# main_board.net
KiCad netlist of a schematic drawn in EAGLE
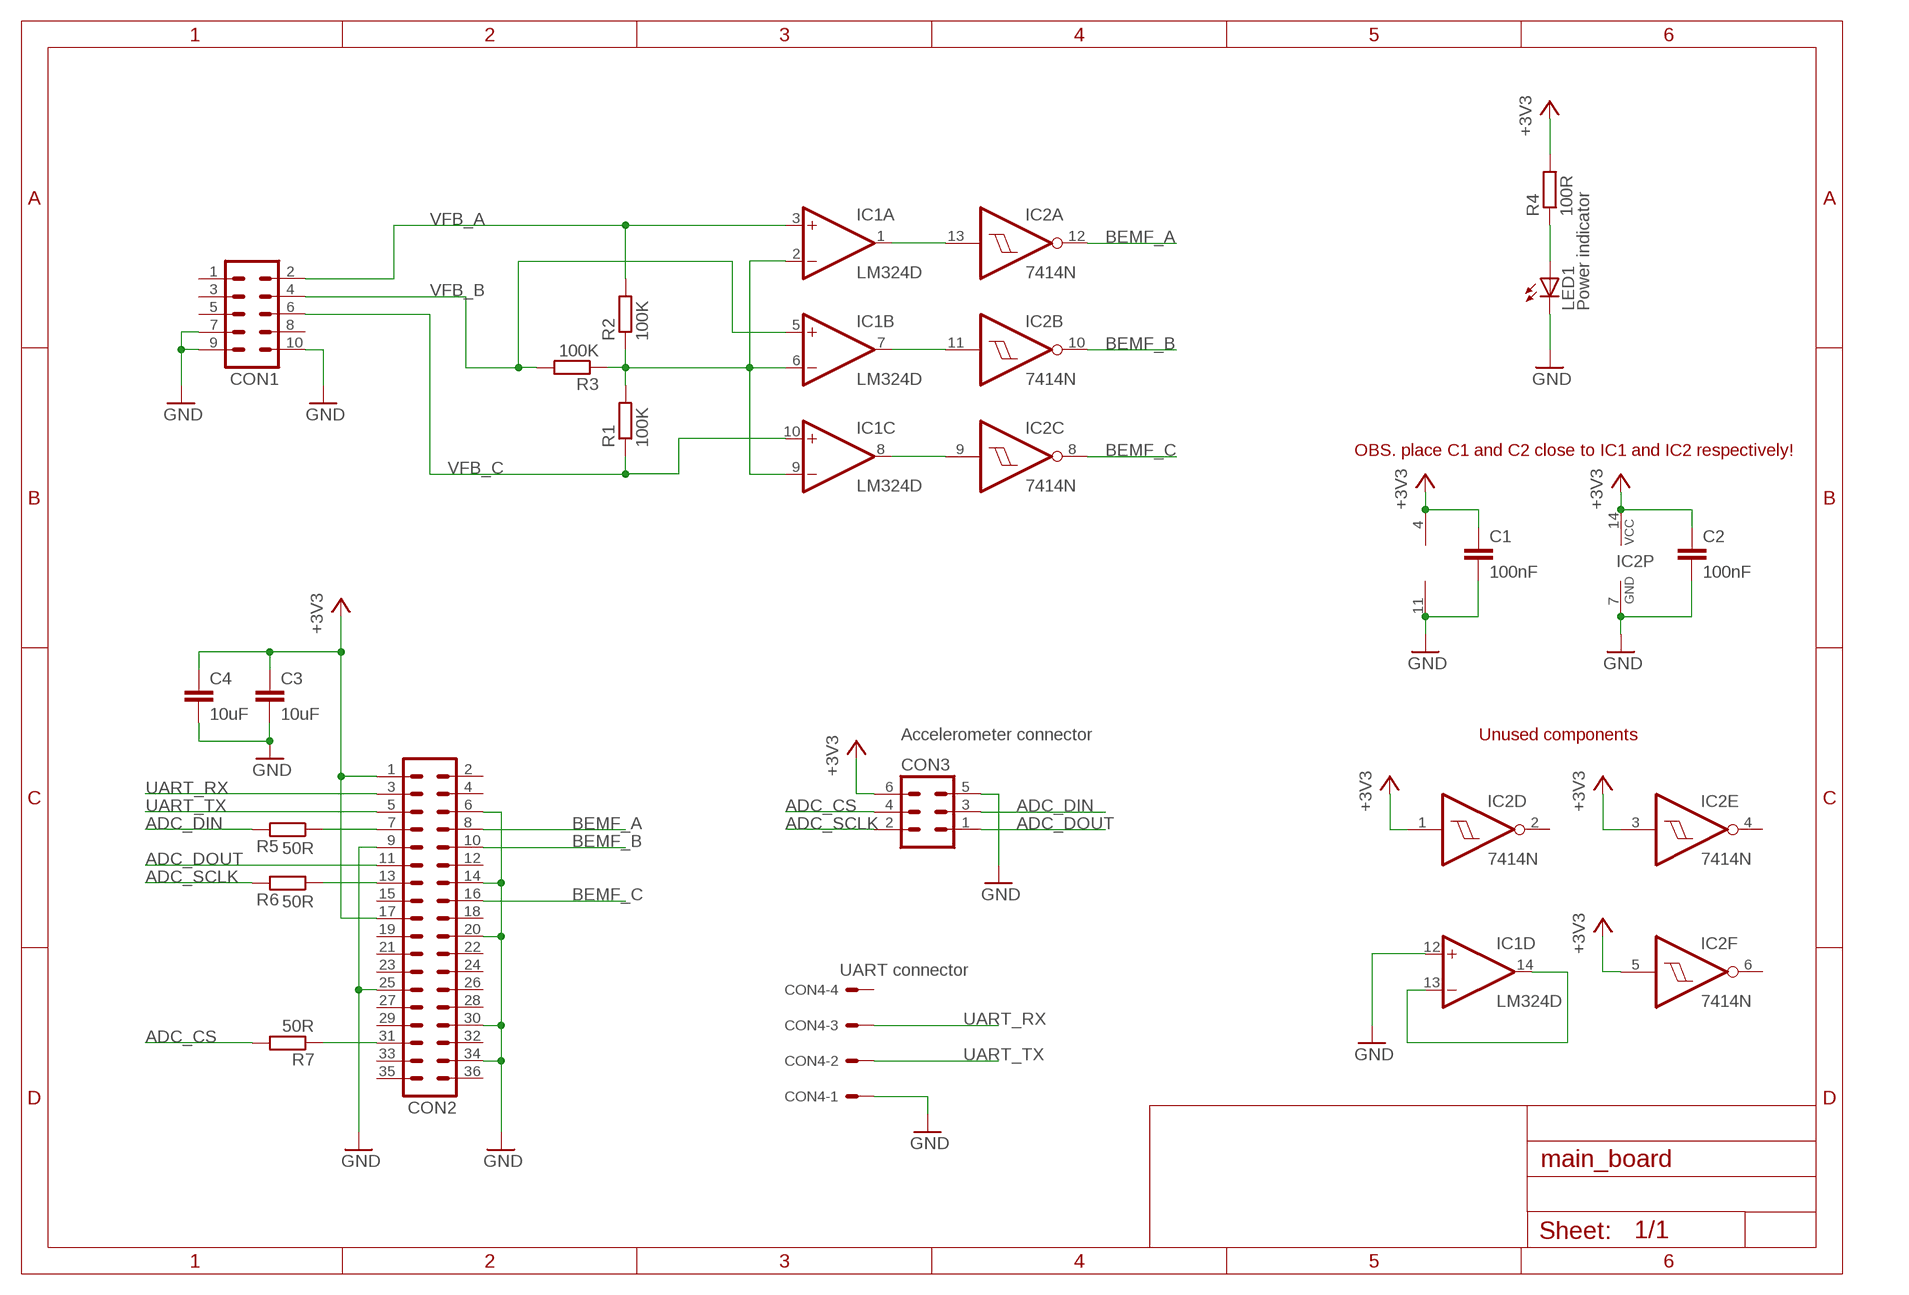
[diagram p0: schematic, sheet 1]

(export (version "E")
  (design (tool "Eeschema 10.0.6"))
  (components
    (comp (ref "C1")
      (value "100nF")
      (footprint "eagle-import:C0805K")
      (libsource (lib "eagle-import") (part "C-EUC0805K"))
    )
    (comp (ref "C2")
      (value "100nF")
      (footprint "eagle-import:C0805K")
      (libsource (lib "eagle-import") (part "C-EUC0805K"))
    )
    (comp (ref "C3")
      (value "10uF")
      (footprint "eagle-import:C1206K")
      (libsource (lib "eagle-import") (part "C-EUC1206K"))
    )
    (comp (ref "C4")
      (value "10uF")
      (footprint "eagle-import:C1206K")
      (libsource (lib "eagle-import") (part "C-EUC1206K"))
    )
    (comp (ref "CON1")
      (value "MA05-2")
      (footprint "eagle-import:MA05-2")
      (libsource (lib "eagle-import") (part "MA05-2"))
    )
    (comp (ref "CON2")
      (value "MA18-2")
      (footprint "eagle-import:MA18-2")
      (libsource (lib "eagle-import") (part "MA18-2"))
    )
    (comp (ref "CON3")
      (value "Accelerometer connector")
      (footprint "eagle-import:ML6")
      (libsource (lib "eagle-import") (part "ML6"))
    )
    (comp (ref "CON4")
      (value "UART connector")
      (footprint "eagle-import:6410-04")
      (libsource (lib "eagle-import") (part "22-?-0427-2041"))
    )
    (comp (ref "IC1")
      (value "LM324D")
      (footprint "eagle-import:SO14")
      (libsource (lib "eagle-import") (part "LM324D"))
    )
    (comp (ref "IC2")
      (value "7414N")
      (footprint "eagle-import:DIL14")
      (libsource (lib "eagle-import") (part "7414N"))
    )
    (comp (ref "LED1")
      (value "Power indicator")
      (footprint "eagle-import:CHIP-LED0805")
      (libsource (lib "eagle-import") (part "LEDCHIP-LED0805"))
    )
    (comp (ref "R1")
      (value "100K")
      (footprint "eagle-import:R0805")
      (libsource (lib "eagle-import") (part "R-EU_R0805"))
    )
    (comp (ref "R2")
      (value "100K")
      (footprint "eagle-import:R0805")
      (libsource (lib "eagle-import") (part "R-EU_R0805"))
    )
    (comp (ref "R3")
      (value "100K")
      (footprint "eagle-import:R0805")
      (libsource (lib "eagle-import") (part "R-EU_R0805"))
    )
    (comp (ref "R4")
      (value "100R")
      (footprint "eagle-import:R0805")
      (libsource (lib "eagle-import") (part "R-EU_R0805"))
    )
    (comp (ref "R5")
      (value "50R")
      (footprint "eagle-import:R0805")
      (libsource (lib "eagle-import") (part "R-EU_R0805"))
    )
    (comp (ref "R6")
      (value "50R")
      (footprint "eagle-import:R0805")
      (libsource (lib "eagle-import") (part "R-EU_R0805"))
    )
    (comp (ref "R7")
      (value "50R")
      (footprint "eagle-import:R0805")
      (libsource (lib "eagle-import") (part "R-EU_R0805"))
    )
  )
  (nets
    (net (code "1") (name "+3V3") (class "Default")
      (node (ref "C1") (pin "1") (pinfunction "1_1") (pintype "passive"))
      (node (ref "C2") (pin "1") (pinfunction "1_1") (pintype "passive"))
      (node (ref "C3") (pin "1") (pinfunction "1_1") (pintype "passive"))
      (node (ref "C4") (pin "1") (pinfunction "1_1") (pintype "passive"))
      (node (ref "CON2") (pin "1") (pinfunction "1_1") (pintype "passive"))
      (node (ref "CON2") (pin "17") (pinfunction "17_17") (pintype "passive"))
      (node (ref "CON3") (pin "6") (pinfunction "6_6") (pintype "passive"))
      (node (ref "IC1") (pin "4") (pinfunction "V+_4") (pintype "power_in"))
      (node (ref "IC2") (pin "1") (pinfunction "I_1") (pintype "input"))
      (node (ref "IC2") (pin "14") (pinfunction "VCC_14") (pintype "power_in"))
      (node (ref "IC2") (pin "3") (pinfunction "I_3") (pintype "input"))
      (node (ref "IC2") (pin "5") (pinfunction "I_5") (pintype "input"))
      (node (ref "R4") (pin "2") (pinfunction "2_2") (pintype "passive"))
    )
    (net (code "2") (name "/ADC_CS") (class "Default")
      (node (ref "CON3") (pin "4") (pinfunction "4_4") (pintype "passive"))
      (node (ref "R7") (pin "2") (pinfunction "2_2") (pintype "passive"))
    )
    (net (code "3") (name "/ADC_DIN") (class "Default")
      (node (ref "CON3") (pin "3") (pinfunction "3_3") (pintype "passive"))
      (node (ref "R5") (pin "2") (pinfunction "2_2") (pintype "passive"))
    )
    (net (code "4") (name "/ADC_DOUT") (class "Default")
      (node (ref "CON2") (pin "11") (pinfunction "11_11") (pintype "passive"))
      (node (ref "CON3") (pin "1") (pinfunction "1_1") (pintype "passive"))
    )
    (net (code "5") (name "/ADC_SCLK") (class "Default")
      (node (ref "CON3") (pin "2") (pinfunction "2_2") (pintype "passive"))
      (node (ref "R6") (pin "2") (pinfunction "2_2") (pintype "passive"))
    )
    (net (code "6") (name "/BEMF_A") (class "Default")
      (node (ref "CON2") (pin "8") (pinfunction "8_8") (pintype "passive"))
      (node (ref "IC2") (pin "12") (pinfunction "O_12") (pintype "output"))
    )
    (net (code "7") (name "/BEMF_B") (class "Default")
      (node (ref "CON2") (pin "10") (pinfunction "10_10") (pintype "passive"))
      (node (ref "IC2") (pin "10") (pinfunction "O_10") (pintype "output"))
    )
    (net (code "8") (name "/BEMF_C") (class "Default")
      (node (ref "CON2") (pin "16") (pinfunction "16_16") (pintype "passive"))
      (node (ref "IC2") (pin "8") (pinfunction "O_8") (pintype "output"))
    )
    (net (code "9") (name "/UART_RX") (class "Default")
      (node (ref "CON2") (pin "3") (pinfunction "3_3") (pintype "passive"))
      (node (ref "CON4") (pin "3") (pinfunction "S_3") (pintype "passive"))
    )
    (net (code "10") (name "/UART_TX") (class "Default")
      (node (ref "CON2") (pin "5") (pinfunction "5_5") (pintype "passive"))
      (node (ref "CON4") (pin "2") (pinfunction "S_2") (pintype "passive"))
    )
    (net (code "11") (name "/VFB_A") (class "Default")
      (node (ref "CON1") (pin "2") (pinfunction "2_2") (pintype "passive"))
      (node (ref "IC1") (pin "3") (pinfunction "+IN_3") (pintype "input"))
      (node (ref "R2") (pin "2") (pinfunction "2_2") (pintype "passive"))
    )
    (net (code "12") (name "/VFB_B") (class "Default")
      (node (ref "CON1") (pin "4") (pinfunction "4_4") (pintype "passive"))
      (node (ref "IC1") (pin "5") (pinfunction "+IN_5") (pintype "input"))
      (node (ref "R3") (pin "2") (pinfunction "2_2") (pintype "passive"))
    )
    (net (code "13") (name "/VFB_C") (class "Default")
      (node (ref "CON1") (pin "6") (pinfunction "6_6") (pintype "passive"))
      (node (ref "IC1") (pin "10") (pinfunction "+IN_10") (pintype "input"))
      (node (ref "R1") (pin "1") (pinfunction "1_1") (pintype "passive"))
    )
    (net (code "14") (name "GND") (class "Default")
      (node (ref "C1") (pin "2") (pinfunction "2_2") (pintype "passive"))
      (node (ref "C2") (pin "2") (pinfunction "2_2") (pintype "passive"))
      (node (ref "C3") (pin "2") (pinfunction "2_2") (pintype "passive"))
      (node (ref "C4") (pin "2") (pinfunction "2_2") (pintype "passive"))
      (node (ref "CON1") (pin "10") (pinfunction "10_10") (pintype "passive"))
      (node (ref "CON1") (pin "7") (pinfunction "7_7") (pintype "passive"))
      (node (ref "CON1") (pin "9") (pinfunction "9_9") (pintype "passive"))
      (node (ref "CON2") (pin "14") (pinfunction "14_14") (pintype "passive"))
      (node (ref "CON2") (pin "20") (pinfunction "20_20") (pintype "passive"))
      (node (ref "CON2") (pin "25") (pinfunction "25_25") (pintype "passive"))
      (node (ref "CON2") (pin "30") (pinfunction "30_30") (pintype "passive"))
      (node (ref "CON2") (pin "34") (pinfunction "34_34") (pintype "passive"))
      (node (ref "CON2") (pin "6") (pinfunction "6_6") (pintype "passive"))
      (node (ref "CON2") (pin "9") (pinfunction "9_9") (pintype "passive"))
      (node (ref "CON3") (pin "5") (pinfunction "5_5") (pintype "passive"))
      (node (ref "CON4") (pin "1") (pinfunction "S_1") (pintype "passive"))
      (node (ref "IC1") (pin "11") (pinfunction "V-_11") (pintype "power_in"))
      (node (ref "IC1") (pin "12") (pinfunction "+IN_12") (pintype "input"))
      (node (ref "IC2") (pin "7") (pinfunction "GND_7") (pintype "power_in"))
      (node (ref "LED1") (pin "C") (pinfunction "C_C") (pintype "passive"))
    )
    (net (code "15") (name "Net-(CON2-Pad7)") (class "Default")
      (node (ref "CON2") (pin "7") (pinfunction "7_7") (pintype "passive"))
      (node (ref "R5") (pin "1") (pinfunction "1_1") (pintype "passive"))
    )
    (net (code "16") (name "Net-(CON2-Pad13)") (class "Default")
      (node (ref "CON2") (pin "13") (pinfunction "13_13") (pintype "passive"))
      (node (ref "R6") (pin "1") (pinfunction "1_1") (pintype "passive"))
    )
    (net (code "17") (name "Net-(CON2-Pad31)") (class "Default")
      (node (ref "CON2") (pin "31") (pinfunction "31_31") (pintype "passive"))
      (node (ref "R7") (pin "1") (pinfunction "1_1") (pintype "passive"))
    )
    (net (code "18") (name "Net-(IC1A--IN)") (class "Default")
      (node (ref "IC1") (pin "2") (pinfunction "-IN_2") (pintype "input"))
      (node (ref "IC1") (pin "6") (pinfunction "-IN_6") (pintype "input"))
      (node (ref "IC1") (pin "9") (pinfunction "-IN_9") (pintype "input"))
      (node (ref "R1") (pin "2") (pinfunction "2_2") (pintype "passive"))
      (node (ref "R2") (pin "1") (pinfunction "1_1") (pintype "passive"))
      (node (ref "R3") (pin "1") (pinfunction "1_1") (pintype "passive"))
    )
    (net (code "19") (name "Net-(IC1A-OUT)") (class "Default")
      (node (ref "IC1") (pin "1") (pinfunction "OUT_1") (pintype "output"))
      (node (ref "IC2") (pin "13") (pinfunction "I_13") (pintype "input"))
    )
    (net (code "20") (name "Net-(IC1B-OUT)") (class "Default")
      (node (ref "IC1") (pin "7") (pinfunction "OUT_7") (pintype "output"))
      (node (ref "IC2") (pin "11") (pinfunction "I_11") (pintype "input"))
    )
    (net (code "21") (name "Net-(IC1C-OUT)") (class "Default")
      (node (ref "IC1") (pin "8") (pinfunction "OUT_8") (pintype "output"))
      (node (ref "IC2") (pin "9") (pinfunction "I_9") (pintype "input"))
    )
    (net (code "22") (name "Net-(IC1D--IN)") (class "Default")
      (node (ref "IC1") (pin "13") (pinfunction "-IN_13") (pintype "input"))
      (node (ref "IC1") (pin "14") (pinfunction "OUT_14") (pintype "output"))
    )
    (net (code "23") (name "Net-(LED1-PadA)") (class "Default")
      (node (ref "LED1") (pin "A") (pinfunction "A_A") (pintype "passive"))
      (node (ref "R4") (pin "1") (pinfunction "1_1") (pintype "passive"))
    )
    (net (code "24") (name "unconnected-(CON1-Pad1)") (class "Default")
      (node (ref "CON1") (pin "1") (pinfunction "1_1") (pintype "passive"))
    )
    (net (code "25") (name "unconnected-(CON1-Pad3)") (class "Default")
      (node (ref "CON1") (pin "3") (pinfunction "3_3") (pintype "passive"))
    )
    (net (code "26") (name "unconnected-(CON1-Pad5)") (class "Default")
      (node (ref "CON1") (pin "5") (pinfunction "5_5") (pintype "passive"))
    )
    (net (code "27") (name "unconnected-(CON1-Pad8)") (class "Default")
      (node (ref "CON1") (pin "8") (pinfunction "8_8") (pintype "passive"))
    )
    (net (code "28") (name "unconnected-(CON2-Pad2)") (class "Default")
      (node (ref "CON2") (pin "2") (pinfunction "2_2") (pintype "passive"))
    )
    (net (code "29") (name "unconnected-(CON2-Pad4)") (class "Default")
      (node (ref "CON2") (pin "4") (pinfunction "4_4") (pintype "passive"))
    )
    (net (code "30") (name "unconnected-(CON2-Pad12)") (class "Default")
      (node (ref "CON2") (pin "12") (pinfunction "12_12") (pintype "passive"))
    )
    (net (code "31") (name "unconnected-(CON2-Pad15)") (class "Default")
      (node (ref "CON2") (pin "15") (pinfunction "15_15") (pintype "passive"))
    )
    (net (code "32") (name "unconnected-(CON2-Pad18)") (class "Default")
      (node (ref "CON2") (pin "18") (pinfunction "18_18") (pintype "passive"))
    )
    (net (code "33") (name "unconnected-(CON2-Pad19)") (class "Default")
      (node (ref "CON2") (pin "19") (pinfunction "19_19") (pintype "passive"))
    )
    (net (code "34") (name "unconnected-(CON2-Pad21)") (class "Default")
      (node (ref "CON2") (pin "21") (pinfunction "21_21") (pintype "passive"))
    )
    (net (code "35") (name "unconnected-(CON2-Pad22)") (class "Default")
      (node (ref "CON2") (pin "22") (pinfunction "22_22") (pintype "passive"))
    )
    (net (code "36") (name "unconnected-(CON2-Pad23)") (class "Default")
      (node (ref "CON2") (pin "23") (pinfunction "23_23") (pintype "passive"))
    )
    (net (code "37") (name "unconnected-(CON2-Pad24)") (class "Default")
      (node (ref "CON2") (pin "24") (pinfunction "24_24") (pintype "passive"))
    )
    (net (code "38") (name "unconnected-(CON2-Pad26)") (class "Default")
      (node (ref "CON2") (pin "26") (pinfunction "26_26") (pintype "passive"))
    )
    (net (code "39") (name "unconnected-(CON2-Pad27)") (class "Default")
      (node (ref "CON2") (pin "27") (pinfunction "27_27") (pintype "passive"))
    )
    (net (code "40") (name "unconnected-(CON2-Pad28)") (class "Default")
      (node (ref "CON2") (pin "28") (pinfunction "28_28") (pintype "passive"))
    )
    (net (code "41") (name "unconnected-(CON2-Pad29)") (class "Default")
      (node (ref "CON2") (pin "29") (pinfunction "29_29") (pintype "passive"))
    )
    (net (code "42") (name "unconnected-(CON2-Pad32)") (class "Default")
      (node (ref "CON2") (pin "32") (pinfunction "32_32") (pintype "passive"))
    )
    (net (code "43") (name "unconnected-(CON2-Pad33)") (class "Default")
      (node (ref "CON2") (pin "33") (pinfunction "33_33") (pintype "passive"))
    )
    (net (code "44") (name "unconnected-(CON2-Pad35)") (class "Default")
      (node (ref "CON2") (pin "35") (pinfunction "35_35") (pintype "passive"))
    )
    (net (code "45") (name "unconnected-(CON2-Pad36)") (class "Default")
      (node (ref "CON2") (pin "36") (pinfunction "36_36") (pintype "passive"))
    )
    (net (code "46") (name "unconnected-(CON4D-S-Pad4)") (class "Default")
      (node (ref "CON4") (pin "4") (pinfunction "S_4") (pintype "passive"))
    )
    (net (code "47") (name "unconnected-(IC2D-O-Pad2)") (class "Default")
      (node (ref "IC2") (pin "2") (pinfunction "O_2") (pintype "output"))
    )
    (net (code "48") (name "unconnected-(IC2E-O-Pad4)") (class "Default")
      (node (ref "IC2") (pin "4") (pinfunction "O_4") (pintype "output"))
    )
    (net (code "49") (name "unconnected-(IC2F-O-Pad6)") (class "Default")
      (node (ref "IC2") (pin "6") (pinfunction "O_6") (pintype "output"))
    )
  )
)
